# DB10005_BatteryStackMonitor.net
KiCad netlist of a schematic drawn in Altium Designer
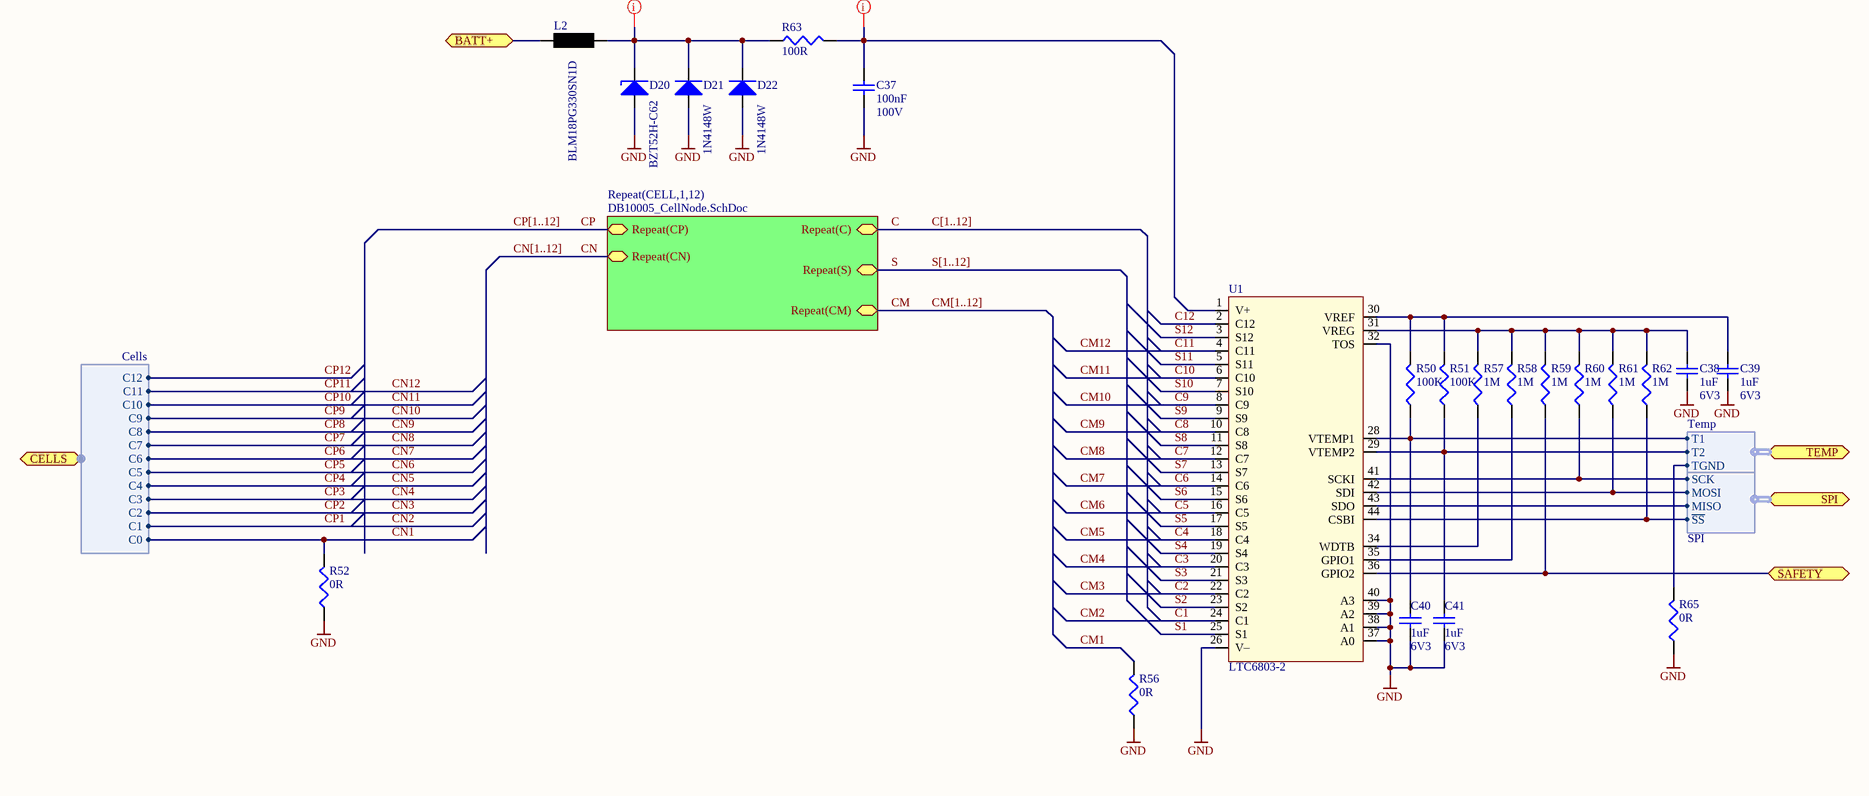
[diagram p0: DB10005_BatteryStackMonitor.SchDoc]

(export (version "E")
  (design (tool "Eeschema 10.0.6"))
  (components
    (comp (ref "C37")
      (value "100nF")
      (footprint "C-0805")
      (description "Capacitor, 100nF, 100V, X7R")
      (fields (field (name "VOLTAGE RATING") "100V"))
      (libsource (lib "AR_Capacitors_Ceramic") (part "100nF/0805/CER/100V"))
    )
    (comp (ref "C38")
      (value "1uF")
      (footprint "C0402")
      (description "Capacitor, 1uF, 6.3V, X5R")
      (fields (field (name "VOLTAGE RATING") "6V3"))
      (libsource (lib "AR_Capacitors_Ceramic") (part "1uF/0402/CER/6.3V"))
    )
    (comp (ref "C39")
      (value "1uF")
      (footprint "C0402")
      (description "Capacitor, 1uF, 6.3V, X5R")
      (fields (field (name "VOLTAGE RATING") "6V3"))
      (libsource (lib "AR_Capacitors_Ceramic") (part "1uF/0402/CER/6.3V"))
    )
    (comp (ref "C40")
      (value "1uF")
      (footprint "C0402")
      (description "Capacitor, 1uF, 6.3V, X5R")
      (fields (field (name "VOLTAGE RATING") "6V3"))
      (libsource (lib "AR_Capacitors_Ceramic") (part "1uF/0402/CER/6.3V"))
    )
    (comp (ref "C41")
      (value "1uF")
      (footprint "C0402")
      (description "Capacitor, 1uF, 6.3V, X5R")
      (fields (field (name "VOLTAGE RATING") "6V3"))
      (libsource (lib "AR_Capacitors_Ceramic") (part "1uF/0402/CER/6.3V"))
    )
    (comp (ref "D20")
      (value "BZT52H-C62")
      (footprint "SOD123W")
      (description "Diode Zener, Vz: 62V, If: 0.25A, Vf: 0.9V")
      (libsource (lib "AR_Diodes") (part "BZT52H-C62,115"))
    )
    (comp (ref "D21")
      (value "1N4148W")
      (footprint "SOD123")
      (description "Diode, Vrrm: 100V, If: 0.15A, Vf: 1V")
      (libsource (lib "AR_Diodes") (part "MMSD4148T1G"))
    )
    (comp (ref "D22")
      (value "1N4148W")
      (footprint "SOD123")
      (description "Diode, Vrrm: 100V, If: 0.15A, Vf: 1V")
      (libsource (lib "AR_Diodes") (part "MMSD4148T1G"))
    )
    (comp (ref "L2")
      (value "BLM18PG330SN1D")
      (footprint "L0603")
      (description "Ferrite Bead, Impedance:33ohm, DC Resistance Max:0.025ohm, DC Current Rating:3A")
      (libsource (lib "AR_Inductors") (part "BLM18PG330SN1D"))
    )
    (comp (ref "R50")
      (value "100K")
      (footprint "0402")
      (description "Resistor, 100k, 0.1%, 0.0625W, 50V, 100PPM, 0402")
      (libsource (lib "AR_Resistors_SMD") (part "100k/0402/0063W/50V"))
    )
    (comp (ref "R51")
      (value "100K")
      (footprint "0402")
      (description "Resistor, 100k, 0.1%, 0.0625W, 50V, 100PPM, 0402")
      (libsource (lib "AR_Resistors_SMD") (part "100k/0402/0063W/50V"))
    )
    (comp (ref "R52")
      (value "0R")
      (footprint "0603")
      (description "Resistor, 0R, 0.1%, 0.063W, 50V, 200PPM, 0603")
      (libsource (lib "AR_Resistors_SMD") (part "0/0603/0063W/50V"))
    )
    (comp (ref "R56")
      (value "0R")
      (footprint "0603")
      (description "Resistor, 0R, 0.1%, 0.063W, 50V, 200PPM, 0603")
      (libsource (lib "AR_Resistors_SMD") (part "0/0603/0063W/50V"))
    )
    (comp (ref "R57")
      (value "1M")
      (footprint "0402")
      (description "Resistor, 1M, 0.1%, 0.0625W, 50V, 100PPM, 0402")
      (libsource (lib "AR_Resistors_SMD") (part "1M/0402/0063W/50V"))
    )
    (comp (ref "R58")
      (value "1M")
      (footprint "0402")
      (description "Resistor, 1M, 0.1%, 0.0625W, 50V, 100PPM, 0402")
      (libsource (lib "AR_Resistors_SMD") (part "1M/0402/0063W/50V"))
    )
    (comp (ref "R59")
      (value "1M")
      (footprint "0402")
      (description "Resistor, 1M, 0.1%, 0.0625W, 50V, 100PPM, 0402")
      (libsource (lib "AR_Resistors_SMD") (part "1M/0402/0063W/50V"))
    )
    (comp (ref "R60")
      (value "1M")
      (footprint "0402")
      (description "Resistor, 1M, 0.1%, 0.0625W, 50V, 100PPM, 0402")
      (libsource (lib "AR_Resistors_SMD") (part "1M/0402/0063W/50V"))
    )
    (comp (ref "R61")
      (value "1M")
      (footprint "0402")
      (description "Resistor, 1M, 0.1%, 0.0625W, 50V, 100PPM, 0402")
      (libsource (lib "AR_Resistors_SMD") (part "1M/0402/0063W/50V"))
    )
    (comp (ref "R62")
      (value "1M")
      (footprint "0402")
      (description "Resistor, 1M, 0.1%, 0.0625W, 50V, 100PPM, 0402")
      (libsource (lib "AR_Resistors_SMD") (part "1M/0402/0063W/50V"))
    )
    (comp (ref "R63")
      (value "100R")
      (footprint "0603")
      (description "Resistor, 100R, 1%, 0.063W, 50V, 200PPM, 0603")
      (libsource (lib "AR_Resistors_SMD") (part "100/0603/0063W/50V"))
    )
    (comp (ref "R65")
      (value "0R")
      (footprint "0603")
      (description "Resistor, 0R, 0.1%, 0.063W, 50V, 200PPM, 0603")
      (libsource (lib "AR_Resistors_SMD") (part "0/0603/0063W/50V"))
    )
    (comp (ref "U1")
      (value "LTC6803-2")
      (footprint "SSOP44")
      (description "Multicell Battery Stack Monitor, T:-40°C to +85°C")
      (libsource (lib "AR_ICs") (part "LTC6803-2"))
    )
  )
  (nets
    (net (code "4") (name "/BATT+") (class "Default")
      (node (ref "L2") (pin "1") (pinfunction "1_1") (pintype "passive"))
    )
    (net (code "6") (name "/C1") (class "Default")
      (node (ref "U1") (pin "24") (pinfunction "C1_24") (pintype "passive"))
    )
    (net (code "7") (name "/C2") (class "Default")
      (node (ref "U1") (pin "22") (pinfunction "C2_22") (pintype "passive"))
    )
    (net (code "8") (name "/C3") (class "Default")
      (node (ref "U1") (pin "20") (pinfunction "C3_20") (pintype "passive"))
    )
    (net (code "9") (name "/C4") (class "Default")
      (node (ref "U1") (pin "18") (pinfunction "C4_18") (pintype "passive"))
    )
    (net (code "10") (name "/C5") (class "Default")
      (node (ref "U1") (pin "16") (pinfunction "C5_16") (pintype "passive"))
    )
    (net (code "11") (name "/C6") (class "Default")
      (node (ref "U1") (pin "14") (pinfunction "C6_14") (pintype "passive"))
    )
    (net (code "12") (name "/C7") (class "Default")
      (node (ref "U1") (pin "12") (pinfunction "C7_12") (pintype "passive"))
    )
    (net (code "13") (name "/C8") (class "Default")
      (node (ref "U1") (pin "10") (pinfunction "C8_10") (pintype "passive"))
    )
    (net (code "14") (name "/C9") (class "Default")
      (node (ref "U1") (pin "8") (pinfunction "C9_8") (pintype "passive"))
    )
    (net (code "15") (name "/C10") (class "Default")
      (node (ref "U1") (pin "6") (pinfunction "C10_6") (pintype "passive"))
    )
    (net (code "16") (name "/C11") (class "Default")
      (node (ref "U1") (pin "4") (pinfunction "C11_4") (pintype "passive"))
    )
    (net (code "17") (name "/C12") (class "Default")
      (node (ref "U1") (pin "2") (pinfunction "C12_2") (pintype "passive"))
    )
    (net (code "19") (name "/CM1") (class "Default")
      (node (ref "R56") (pin "2") (pinfunction "2_2") (pintype "passive"))
    )
    (net (code "22") (name "/CN1") (class "Default")
      (node (ref "R52") (pin "2") (pinfunction "2_2") (pintype "passive"))
    )
    (net (code "39") (name "/MISO") (class "Default")
      (node (ref "U1") (pin "43") (pinfunction "SDO_43") (pintype "passive"))
    )
    (net (code "40") (name "/MOSI") (class "Default")
      (node (ref "R61") (pin "1") (pinfunction "1_1") (pintype "passive"))
      (node (ref "U1") (pin "42") (pinfunction "SDI_42") (pintype "passive"))
    )
    (net (code "42") (name "/S1") (class "Default")
      (node (ref "U1") (pin "25") (pinfunction "S1_25") (pintype "passive"))
    )
    (net (code "43") (name "/S2") (class "Default")
      (node (ref "U1") (pin "23") (pinfunction "S2_23") (pintype "passive"))
    )
    (net (code "44") (name "/S3") (class "Default")
      (node (ref "U1") (pin "21") (pinfunction "S3_21") (pintype "passive"))
    )
    (net (code "45") (name "/S4") (class "Default")
      (node (ref "U1") (pin "19") (pinfunction "S4_19") (pintype "passive"))
    )
    (net (code "46") (name "/S5") (class "Default")
      (node (ref "U1") (pin "17") (pinfunction "S5_17") (pintype "passive"))
    )
    (net (code "47") (name "/S6") (class "Default")
      (node (ref "U1") (pin "15") (pinfunction "S6_15") (pintype "passive"))
    )
    (net (code "48") (name "/S7") (class "Default")
      (node (ref "U1") (pin "13") (pinfunction "S7_13") (pintype "passive"))
    )
    (net (code "49") (name "/S8") (class "Default")
      (node (ref "U1") (pin "11") (pinfunction "S8_11") (pintype "passive"))
    )
    (net (code "50") (name "/S9") (class "Default")
      (node (ref "U1") (pin "9") (pinfunction "S9_9") (pintype "passive"))
    )
    (net (code "51") (name "/S10") (class "Default")
      (node (ref "U1") (pin "7") (pinfunction "S10_7") (pintype "passive"))
    )
    (net (code "52") (name "/S11") (class "Default")
      (node (ref "U1") (pin "5") (pinfunction "S11_5") (pintype "passive"))
    )
    (net (code "53") (name "/S12") (class "Default")
      (node (ref "U1") (pin "3") (pinfunction "S12_3") (pintype "passive"))
    )
    (net (code "54") (name "/SAFETY") (class "Default")
      (node (ref "R59") (pin "1") (pinfunction "1_1") (pintype "passive"))
      (node (ref "U1") (pin "36") (pinfunction "GPIO2_36") (pintype "passive"))
    )
    (net (code "55") (name "/SCK") (class "Default")
      (node (ref "R60") (pin "1") (pinfunction "1_1") (pintype "passive"))
      (node (ref "U1") (pin "41") (pinfunction "SCKI_41") (pintype "passive"))
    )
    (net (code "57") (name "/T1") (class "Default")
      (node (ref "C40") (pin "2") (pinfunction "2_2") (pintype "passive"))
      (node (ref "R50") (pin "1") (pinfunction "1_1") (pintype "passive"))
      (node (ref "U1") (pin "28") (pinfunction "VTEMP1_28") (pintype "passive"))
    )
    (net (code "58") (name "/T2") (class "Default")
      (node (ref "C41") (pin "2") (pinfunction "2_2") (pintype "passive"))
      (node (ref "R51") (pin "1") (pinfunction "1_1") (pintype "passive"))
      (node (ref "U1") (pin "29") (pinfunction "VTEMP2_29") (pintype "passive"))
    )
    (net (code "59") (name "/TGND") (class "Default")
      (node (ref "R65") (pin "2") (pinfunction "2_2") (pintype "passive"))
    )
    (net (code "63") (name "/~{SS}") (class "Default")
      (node (ref "R62") (pin "1") (pinfunction "1_1") (pintype "passive"))
      (node (ref "U1") (pin "44") (pinfunction "CSBI_44") (pintype "passive"))
    )
    (net (code "64") (name "GND") (class "Default")
      (node (ref "C37") (pin "1") (pinfunction "1_1") (pintype "passive"))
      (node (ref "C38") (pin "1") (pinfunction "1_1") (pintype "passive"))
      (node (ref "C39") (pin "1") (pinfunction "1_1") (pintype "passive"))
      (node (ref "C40") (pin "1") (pinfunction "1_1") (pintype "passive"))
      (node (ref "C41") (pin "1") (pinfunction "1_1") (pintype "passive"))
      (node (ref "D20") (pin "1") (pinfunction "1_1") (pintype "passive"))
      (node (ref "D21") (pin "1") (pinfunction "A_1") (pintype "passive"))
      (node (ref "D22") (pin "1") (pinfunction "A_1") (pintype "passive"))
      (node (ref "R52") (pin "1") (pinfunction "1_1") (pintype "passive"))
      (node (ref "R56") (pin "1") (pinfunction "1_1") (pintype "passive"))
      (node (ref "R65") (pin "1") (pinfunction "1_1") (pintype "passive"))
      (node (ref "U1") (pin "26") (pinfunction "V–_26") (pintype "passive"))
      (node (ref "U1") (pin "32") (pinfunction "TOS_32") (pintype "passive"))
      (node (ref "U1") (pin "37") (pinfunction "A0_37") (pintype "passive"))
      (node (ref "U1") (pin "38") (pinfunction "A1_38") (pintype "passive"))
      (node (ref "U1") (pin "39") (pinfunction "A2_39") (pintype "passive"))
      (node (ref "U1") (pin "40") (pinfunction "A3_40") (pintype "passive"))
    )
    (net (code "65") (name "Net-(D21-K)") (class "Default")
      (node (ref "D20") (pin "2") (pinfunction "2_2") (pintype "passive"))
      (node (ref "D21") (pin "2") (pinfunction "K_2") (pintype "passive"))
      (node (ref "D22") (pin "2") (pinfunction "K_2") (pintype "passive"))
      (node (ref "L2") (pin "2") (pinfunction "2_2") (pintype "passive"))
      (node (ref "R63") (pin "1") (pinfunction "1_1") (pintype "passive"))
    )
    (net (code "66") (name "Net-(U1-GPIO1)") (class "Default")
      (node (ref "R58") (pin "1") (pinfunction "1_1") (pintype "passive"))
      (node (ref "U1") (pin "35") (pinfunction "GPIO1_35") (pintype "passive"))
    )
    (net (code "67") (name "Net-(U1-V+)") (class "Default")
      (node (ref "C37") (pin "2") (pinfunction "2_2") (pintype "passive"))
      (node (ref "R63") (pin "2") (pinfunction "2_2") (pintype "passive"))
      (node (ref "U1") (pin "1") (pinfunction "V+_1") (pintype "passive"))
    )
    (net (code "68") (name "Net-(U1-VREF)") (class "Default")
      (node (ref "C39") (pin "2") (pinfunction "2_2") (pintype "passive"))
      (node (ref "R50") (pin "2") (pinfunction "2_2") (pintype "passive"))
      (node (ref "R51") (pin "2") (pinfunction "2_2") (pintype "passive"))
      (node (ref "U1") (pin "30") (pinfunction "VREF_30") (pintype "passive"))
    )
    (net (code "69") (name "Net-(U1-VREG)") (class "Default")
      (node (ref "C38") (pin "2") (pinfunction "2_2") (pintype "passive"))
      (node (ref "R57") (pin "2") (pinfunction "2_2") (pintype "passive"))
      (node (ref "R58") (pin "2") (pinfunction "2_2") (pintype "passive"))
      (node (ref "R59") (pin "2") (pinfunction "2_2") (pintype "passive"))
      (node (ref "R60") (pin "2") (pinfunction "2_2") (pintype "passive"))
      (node (ref "R61") (pin "2") (pinfunction "2_2") (pintype "passive"))
      (node (ref "R62") (pin "2") (pinfunction "2_2") (pintype "passive"))
      (node (ref "U1") (pin "31") (pinfunction "VREG_31") (pintype "passive"))
    )
    (net (code "70") (name "Net-(U1-WDTB)") (class "Default")
      (node (ref "R57") (pin "1") (pinfunction "1_1") (pintype "passive"))
      (node (ref "U1") (pin "34") (pinfunction "WDTB_34") (pintype "passive"))
    )
  )
)
